# Schematic_ver01.net
KiCad netlist of a schematic drawn in Altium Designer
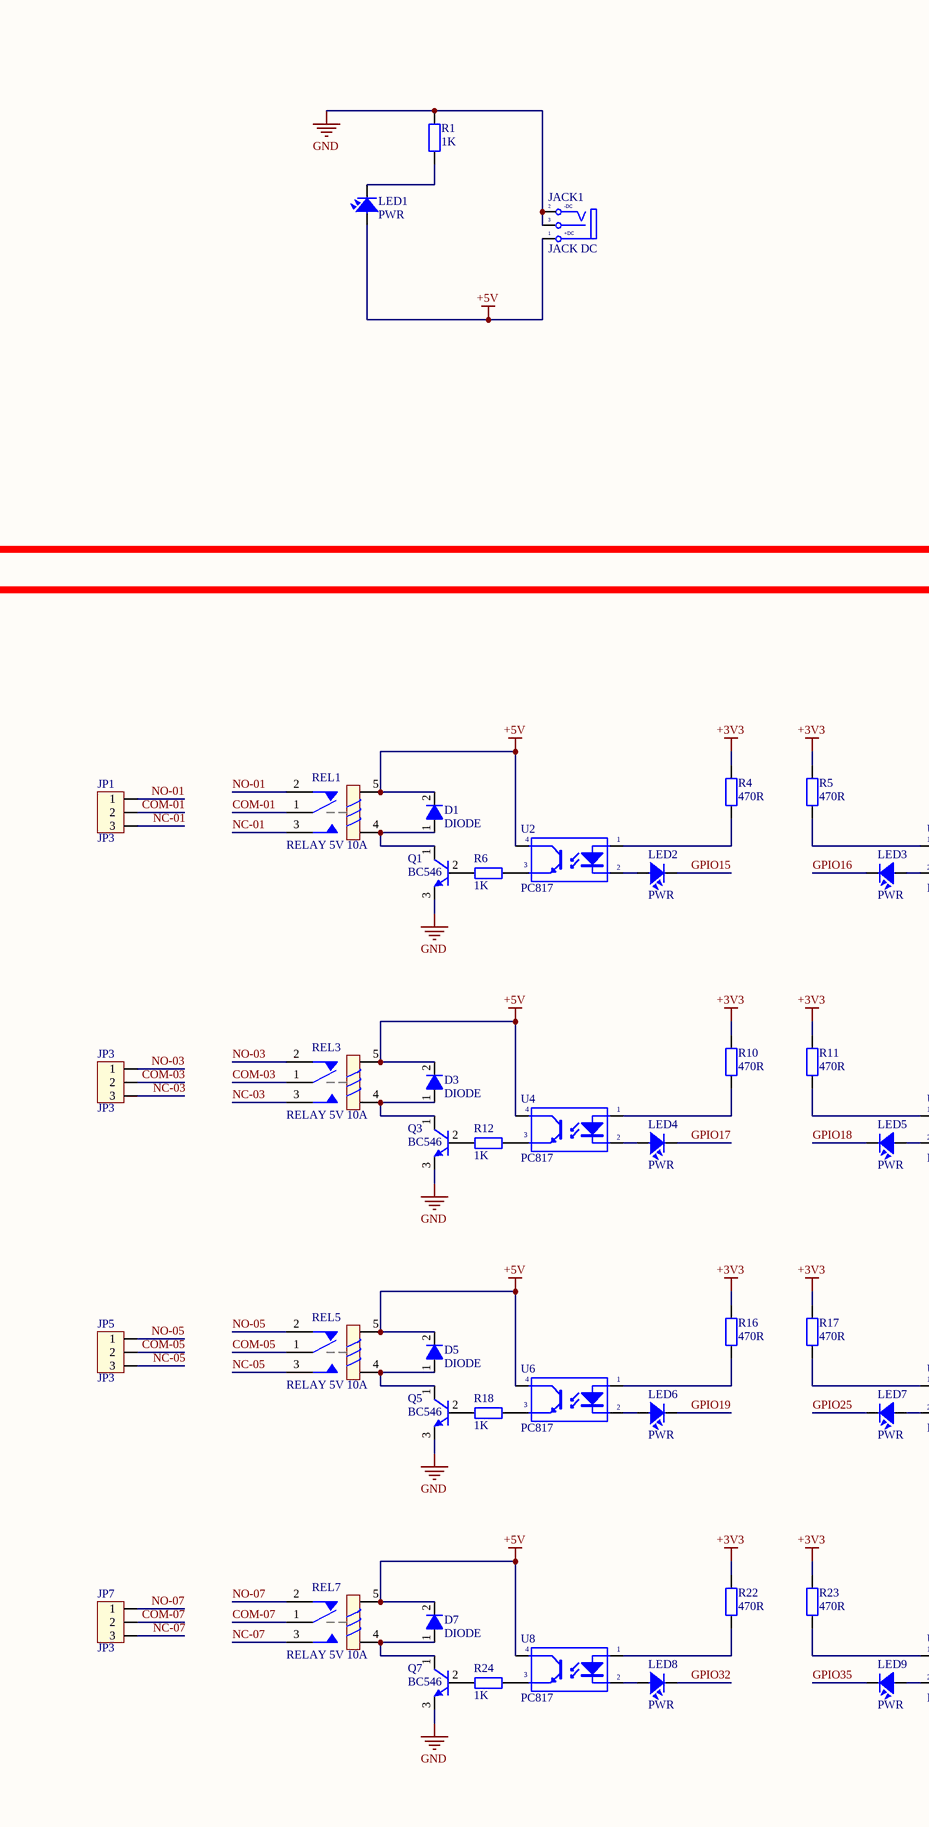
[diagram p0: Schematic_ver01.SchDoc, left]
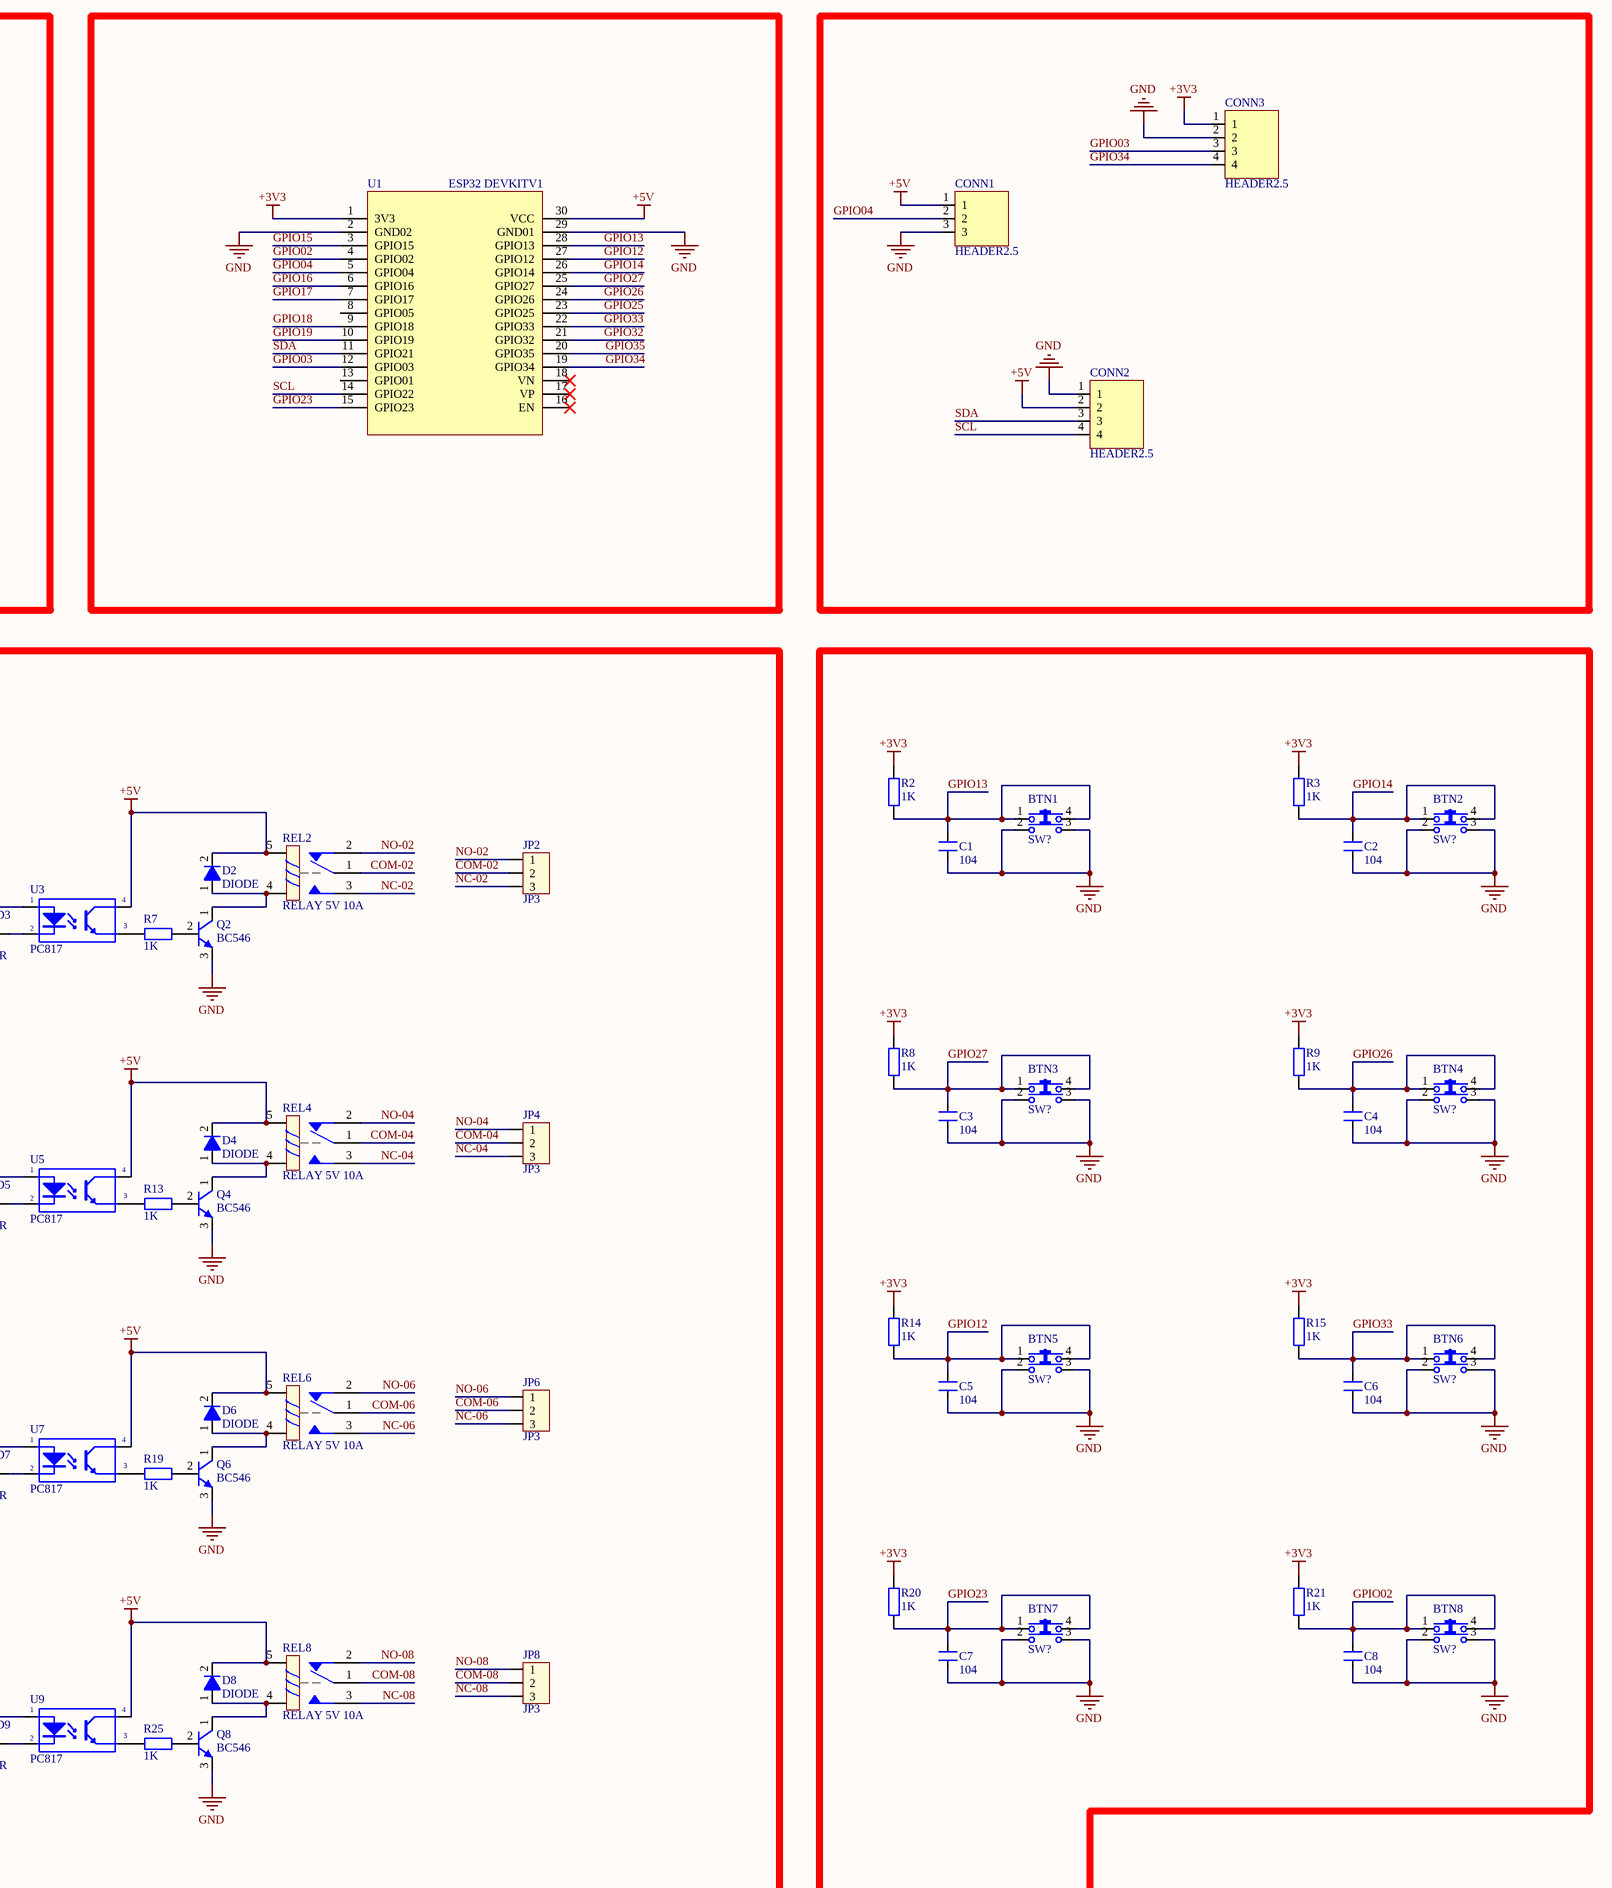
[diagram p1: Schematic_ver01.SchDoc, right]

(export (version "E")
  (design (tool "Eeschema 10.0.6"))
  (components
    (comp (ref "BTN1")
      (value "SW?")
      (footprint "SW-4P-S")
      (libsource (lib "LibSchematicAltiumKieN") (part "button-4"))
    )
    (comp (ref "BTN2")
      (value "SW?")
      (footprint "SW-4P-S")
      (libsource (lib "LibSchematicAltiumKieN") (part "button-4"))
    )
    (comp (ref "BTN3")
      (value "SW?")
      (footprint "SW-4P-S")
      (libsource (lib "LibSchematicAltiumKieN") (part "button-4"))
    )
    (comp (ref "BTN4")
      (value "SW?")
      (footprint "SW-4P-S")
      (libsource (lib "LibSchematicAltiumKieN") (part "button-4"))
    )
    (comp (ref "BTN5")
      (value "SW?")
      (footprint "SW-4P-S")
      (libsource (lib "LibSchematicAltiumKieN") (part "button-4"))
    )
    (comp (ref "BTN6")
      (value "SW?")
      (footprint "SW-4P-S")
      (libsource (lib "LibSchematicAltiumKieN") (part "button-4"))
    )
    (comp (ref "BTN7")
      (value "SW?")
      (footprint "SW-4P-S")
      (libsource (lib "LibSchematicAltiumKieN") (part "button-4"))
    )
    (comp (ref "BTN8")
      (value "SW?")
      (footprint "SW-4P-S")
      (libsource (lib "LibSchematicAltiumKieN") (part "button-4"))
    )
    (comp (ref "C1")
      (value "104")
      (footprint "0805 CAP")
      (libsource (lib "LibSchematicAltiumKieN") (part "CAP CERAMIC"))
    )
    (comp (ref "C2")
      (value "104")
      (footprint "0805 CAP")
      (libsource (lib "LibSchematicAltiumKieN") (part "CAP CERAMIC"))
    )
    (comp (ref "C3")
      (value "104")
      (footprint "0805 CAP")
      (libsource (lib "LibSchematicAltiumKieN") (part "CAP CERAMIC"))
    )
    (comp (ref "C4")
      (value "104")
      (footprint "0805 CAP")
      (libsource (lib "LibSchematicAltiumKieN") (part "CAP CERAMIC"))
    )
    (comp (ref "C5")
      (value "104")
      (footprint "0805 CAP")
      (libsource (lib "LibSchematicAltiumKieN") (part "CAP CERAMIC"))
    )
    (comp (ref "C6")
      (value "104")
      (footprint "0805 CAP")
      (libsource (lib "LibSchematicAltiumKieN") (part "CAP CERAMIC"))
    )
    (comp (ref "C7")
      (value "104")
      (footprint "0805 CAP")
      (libsource (lib "LibSchematicAltiumKieN") (part "CAP CERAMIC"))
    )
    (comp (ref "C8")
      (value "104")
      (footprint "0805 CAP")
      (libsource (lib "LibSchematicAltiumKieN") (part "CAP CERAMIC"))
    )
    (comp (ref "CONN1")
      (value "HEADER2.5")
      (footprint "CONN3")
      (description "CONN HEADER VERT 3POS 2.5MM")
      (libsource (lib "LibSchematicAltiumKieN") (part "B3B-XH-A"))
    )
    (comp (ref "CONN2")
      (value "HEADER2.5")
      (footprint "CONN4")
      (description "CONN HEADER VERT 4POS 2.5MM")
      (libsource (lib "LibSchematicAltiumKieN") (part "B4B-XH-A"))
    )
    (comp (ref "CONN3")
      (value "HEADER2.5")
      (footprint "CONN4")
      (description "CONN HEADER VERT 4POS 2.5MM")
      (libsource (lib "LibSchematicAltiumKieN") (part "B4B-XH-A"))
    )
    (comp (ref "D1")
      (value "DIODE")
      (footprint "SOD-123")
      (libsource (lib "LibSchematicAltiumKieN") (part "DIODE"))
    )
    (comp (ref "D2")
      (value "DIODE")
      (footprint "SOD-123")
      (libsource (lib "LibSchematicAltiumKieN") (part "DIODE"))
    )
    (comp (ref "D3")
      (value "DIODE")
      (footprint "SOD-123")
      (libsource (lib "LibSchematicAltiumKieN") (part "DIODE"))
    )
    (comp (ref "D4")
      (value "DIODE")
      (footprint "SOD-123")
      (libsource (lib "LibSchematicAltiumKieN") (part "DIODE"))
    )
    (comp (ref "D5")
      (value "DIODE")
      (footprint "SOD-123")
      (libsource (lib "LibSchematicAltiumKieN") (part "DIODE"))
    )
    (comp (ref "D6")
      (value "DIODE")
      (footprint "SOD-123")
      (libsource (lib "LibSchematicAltiumKieN") (part "DIODE"))
    )
    (comp (ref "D7")
      (value "DIODE")
      (footprint "SOD-123")
      (libsource (lib "LibSchematicAltiumKieN") (part "DIODE"))
    )
    (comp (ref "D8")
      (value "DIODE")
      (footprint "SOD-123")
      (libsource (lib "LibSchematicAltiumKieN") (part "DIODE"))
    )
    (comp (ref "JACK1")
      (value "JACK DC")
      (footprint "JACK-DC")
      (libsource (lib "LibSchematicAltiumKieN") (part "JACK DC"))
    )
    (comp (ref "JP1")
      (value "JP3")
      (footprint "HED3")
      (description "Connector 3")
      (libsource (lib "") (part "CON3_1"))
    )
    (comp (ref "JP2")
      (value "JP3")
      (footprint "HED3")
      (description "Connector 3")
      (libsource (lib "LibSchematicAltiumKieN") (part "CON3"))
    )
    (comp (ref "JP3")
      (value "JP3")
      (footprint "HED3")
      (description "Connector 3")
      (libsource (lib "") (part "CON3_1"))
    )
    (comp (ref "JP4")
      (value "JP3")
      (footprint "HED3")
      (description "Connector 3")
      (libsource (lib "LibSchematicAltiumKieN") (part "CON3"))
    )
    (comp (ref "JP5")
      (value "JP3")
      (footprint "HED3")
      (description "Connector 3")
      (libsource (lib "") (part "CON3_1"))
    )
    (comp (ref "JP6")
      (value "JP3")
      (footprint "HED3")
      (description "Connector 3")
      (libsource (lib "LibSchematicAltiumKieN") (part "CON3"))
    )
    (comp (ref "JP7")
      (value "JP3")
      (footprint "HED3")
      (description "Connector 3")
      (libsource (lib "") (part "CON3_1"))
    )
    (comp (ref "JP8")
      (value "JP3")
      (footprint "HED3")
      (description "Connector 3")
      (libsource (lib "LibSchematicAltiumKieN") (part "CON3"))
    )
    (comp (ref "LED1")
      (value "PWR")
      (footprint "0805 LED")
      (description "Single color LED")
      (libsource (lib "LibSchematicAltiumKieN") (part "LED"))
    )
    (comp (ref "LED2")
      (value "PWR")
      (footprint "0805 LED")
      (description "Single color LED")
      (libsource (lib "LibSchematicAltiumKieN") (part "LED"))
    )
    (comp (ref "LED3")
      (value "PWR")
      (footprint "0805 LED")
      (description "Single color LED")
      (libsource (lib "LibSchematicAltiumKieN") (part "LED"))
    )
    (comp (ref "LED4")
      (value "PWR")
      (footprint "0805 LED")
      (description "Single color LED")
      (libsource (lib "LibSchematicAltiumKieN") (part "LED"))
    )
    (comp (ref "LED5")
      (value "PWR")
      (footprint "0805 LED")
      (description "Single color LED")
      (libsource (lib "LibSchematicAltiumKieN") (part "LED"))
    )
    (comp (ref "LED6")
      (value "PWR")
      (footprint "0805 LED")
      (description "Single color LED")
      (libsource (lib "LibSchematicAltiumKieN") (part "LED"))
    )
    (comp (ref "LED7")
      (value "PWR")
      (footprint "0805 LED")
      (description "Single color LED")
      (libsource (lib "LibSchematicAltiumKieN") (part "LED"))
    )
    (comp (ref "LED8")
      (value "PWR")
      (footprint "0805 LED")
      (description "Single color LED")
      (libsource (lib "LibSchematicAltiumKieN") (part "LED"))
    )
    (comp (ref "LED9")
      (value "PWR")
      (footprint "0805 LED")
      (description "Single color LED")
      (libsource (lib "LibSchematicAltiumKieN") (part "LED"))
    )
    (comp (ref "Q1")
      (value "BC546")
      (footprint "TO92")
      (description "TRANS NPN 45V 0.1A TO-92-3")
      (libsource (lib "LibSchematicAltiumKieN") (part "BC547"))
    )
    (comp (ref "Q2")
      (value "BC546")
      (footprint "TO92")
      (description "TRANS NPN 45V 0.1A TO-92-3")
      (libsource (lib "LibSchematicAltiumKieN") (part "BC547"))
    )
    (comp (ref "Q3")
      (value "BC546")
      (footprint "TO92")
      (description "TRANS NPN 45V 0.1A TO-92-3")
      (libsource (lib "LibSchematicAltiumKieN") (part "BC547"))
    )
    (comp (ref "Q4")
      (value "BC546")
      (footprint "TO92")
      (description "TRANS NPN 45V 0.1A TO-92-3")
      (libsource (lib "LibSchematicAltiumKieN") (part "BC547"))
    )
    (comp (ref "Q5")
      (value "BC546")
      (footprint "TO92")
      (description "TRANS NPN 45V 0.1A TO-92-3")
      (libsource (lib "LibSchematicAltiumKieN") (part "BC547"))
    )
    (comp (ref "Q6")
      (value "BC546")
      (footprint "TO92")
      (description "TRANS NPN 45V 0.1A TO-92-3")
      (libsource (lib "LibSchematicAltiumKieN") (part "BC547"))
    )
    (comp (ref "Q7")
      (value "BC546")
      (footprint "TO92")
      (description "TRANS NPN 45V 0.1A TO-92-3")
      (libsource (lib "LibSchematicAltiumKieN") (part "BC547"))
    )
    (comp (ref "Q8")
      (value "BC546")
      (footprint "TO92")
      (description "TRANS NPN 45V 0.1A TO-92-3")
      (libsource (lib "LibSchematicAltiumKieN") (part "BC547"))
    )
    (comp (ref "R1")
      (value "1K")
      (footprint "0805 RESISTOR")
      (description "Resistor")
      (libsource (lib "LibSchematicAltiumKieN") (part "RESISTOR"))
    )
    (comp (ref "R2")
      (value "1K")
      (footprint "0805 RESISTOR")
      (description "Resistor")
      (libsource (lib "LibSchematicAltiumKieN") (part "RESISTOR"))
    )
    (comp (ref "R3")
      (value "1K")
      (footprint "0805 RESISTOR")
      (description "Resistor")
      (libsource (lib "LibSchematicAltiumKieN") (part "RESISTOR"))
    )
    (comp (ref "R4")
      (value "470R")
      (footprint "0805 RESISTOR")
      (description "Resistor")
      (libsource (lib "LibSchematicAltiumKieN") (part "RESISTOR"))
    )
    (comp (ref "R5")
      (value "470R")
      (footprint "0805 RESISTOR")
      (description "Resistor")
      (libsource (lib "LibSchematicAltiumKieN") (part "RESISTOR"))
    )
    (comp (ref "R6")
      (value "1K")
      (footprint "0805 RESISTOR")
      (description "Resistor")
      (libsource (lib "LibSchematicAltiumKieN") (part "RESISTOR"))
    )
    (comp (ref "R7")
      (value "1K")
      (footprint "0805 RESISTOR")
      (description "Resistor")
      (libsource (lib "LibSchematicAltiumKieN") (part "RESISTOR"))
    )
    (comp (ref "R8")
      (value "1K")
      (footprint "0805 RESISTOR")
      (description "Resistor")
      (libsource (lib "LibSchematicAltiumKieN") (part "RESISTOR"))
    )
    (comp (ref "R9")
      (value "1K")
      (footprint "0805 RESISTOR")
      (description "Resistor")
      (libsource (lib "LibSchematicAltiumKieN") (part "RESISTOR"))
    )
    (comp (ref "R10")
      (value "470R")
      (footprint "0805 RESISTOR")
      (description "Resistor")
      (libsource (lib "LibSchematicAltiumKieN") (part "RESISTOR"))
    )
    (comp (ref "R11")
      (value "470R")
      (footprint "0805 RESISTOR")
      (description "Resistor")
      (libsource (lib "LibSchematicAltiumKieN") (part "RESISTOR"))
    )
    (comp (ref "R12")
      (value "1K")
      (footprint "0805 RESISTOR")
      (description "Resistor")
      (libsource (lib "LibSchematicAltiumKieN") (part "RESISTOR"))
    )
    (comp (ref "R13")
      (value "1K")
      (footprint "0805 RESISTOR")
      (description "Resistor")
      (libsource (lib "LibSchematicAltiumKieN") (part "RESISTOR"))
    )
    (comp (ref "R14")
      (value "1K")
      (footprint "0805 RESISTOR")
      (description "Resistor")
      (libsource (lib "LibSchematicAltiumKieN") (part "RESISTOR"))
    )
    (comp (ref "R15")
      (value "1K")
      (footprint "0805 RESISTOR")
      (description "Resistor")
      (libsource (lib "LibSchematicAltiumKieN") (part "RESISTOR"))
    )
    (comp (ref "R16")
      (value "470R")
      (footprint "0805 RESISTOR")
      (description "Resistor")
      (libsource (lib "LibSchematicAltiumKieN") (part "RESISTOR"))
    )
    (comp (ref "R17")
      (value "470R")
      (footprint "0805 RESISTOR")
      (description "Resistor")
      (libsource (lib "LibSchematicAltiumKieN") (part "RESISTOR"))
    )
    (comp (ref "R18")
      (value "1K")
      (footprint "0805 RESISTOR")
      (description "Resistor")
      (libsource (lib "LibSchematicAltiumKieN") (part "RESISTOR"))
    )
    (comp (ref "R19")
      (value "1K")
      (footprint "0805 RESISTOR")
      (description "Resistor")
      (libsource (lib "LibSchematicAltiumKieN") (part "RESISTOR"))
    )
    (comp (ref "R20")
      (value "1K")
      (footprint "0805 RESISTOR")
      (description "Resistor")
      (libsource (lib "LibSchematicAltiumKieN") (part "RESISTOR"))
    )
    (comp (ref "R21")
      (value "1K")
      (footprint "0805 RESISTOR")
      (description "Resistor")
      (libsource (lib "LibSchematicAltiumKieN") (part "RESISTOR"))
    )
    (comp (ref "R22")
      (value "470R")
      (footprint "0805 RESISTOR")
      (description "Resistor")
      (libsource (lib "LibSchematicAltiumKieN") (part "RESISTOR"))
    )
    (comp (ref "R23")
      (value "470R")
      (footprint "0805 RESISTOR")
      (description "Resistor")
      (libsource (lib "LibSchematicAltiumKieN") (part "RESISTOR"))
    )
    (comp (ref "R24")
      (value "1K")
      (footprint "0805 RESISTOR")
      (description "Resistor")
      (libsource (lib "LibSchematicAltiumKieN") (part "RESISTOR"))
    )
    (comp (ref "R25")
      (value "1K")
      (footprint "0805 RESISTOR")
      (description "Resistor")
      (libsource (lib "LibSchematicAltiumKieN") (part "RESISTOR"))
    )
    (comp (ref "REL1")
      (value "RELAY 5V 10A")
      (footprint "RELAY 5V-10A")
      (libsource (lib "") (part "RELAY 5V 10A_1"))
    )
    (comp (ref "REL2")
      (value "RELAY 5V 10A")
      (footprint "RELAY 5V-10A")
      (libsource (lib "LibSchematicAltiumKieN") (part "RELAY 5V 10A"))
    )
    (comp (ref "REL3")
      (value "RELAY 5V 10A")
      (footprint "RELAY 5V-10A")
      (libsource (lib "") (part "RELAY 5V 10A_1"))
    )
    (comp (ref "REL4")
      (value "RELAY 5V 10A")
      (footprint "RELAY 5V-10A")
      (libsource (lib "LibSchematicAltiumKieN") (part "RELAY 5V 10A"))
    )
    (comp (ref "REL5")
      (value "RELAY 5V 10A")
      (footprint "RELAY 5V-10A")
      (libsource (lib "") (part "RELAY 5V 10A_1"))
    )
    (comp (ref "REL6")
      (value "RELAY 5V 10A")
      (footprint "RELAY 5V-10A")
      (libsource (lib "LibSchematicAltiumKieN") (part "RELAY 5V 10A"))
    )
    (comp (ref "REL7")
      (value "RELAY 5V 10A")
      (footprint "RELAY 5V-10A")
      (libsource (lib "") (part "RELAY 5V 10A_1"))
    )
    (comp (ref "REL8")
      (value "RELAY 5V 10A")
      (footprint "RELAY 5V-10A")
      (libsource (lib "LibSchematicAltiumKieN") (part "RELAY 5V 10A"))
    )
    (comp (ref "U1")
      (value "ESP32 DEVKITV1")
      (footprint "ESP32-PIN")
      (libsource (lib "LibSchematicAltiumKieN") (part "ESP32 DEVKITV1"))
    )
    (comp (ref "U2")
      (value "PC817")
      (footprint "DIP4/W0.3")
      (description "Single Opto")
      (libsource (lib "LibSchematicAltiumKieN") (part "PC817"))
    )
    (comp (ref "U3")
      (value "PC817")
      (footprint "DIP4/W0.3")
      (description "Single Opto")
      (libsource (lib "LibSchematicAltiumKieN") (part "PC817"))
    )
    (comp (ref "U4")
      (value "PC817")
      (footprint "DIP4/W0.3")
      (description "Single Opto")
      (libsource (lib "LibSchematicAltiumKieN") (part "PC817"))
    )
    (comp (ref "U5")
      (value "PC817")
      (footprint "DIP4/W0.3")
      (description "Single Opto")
      (libsource (lib "LibSchematicAltiumKieN") (part "PC817"))
    )
    (comp (ref "U6")
      (value "PC817")
      (footprint "DIP4/W0.3")
      (description "Single Opto")
      (libsource (lib "LibSchematicAltiumKieN") (part "PC817"))
    )
    (comp (ref "U7")
      (value "PC817")
      (footprint "DIP4/W0.3")
      (description "Single Opto")
      (libsource (lib "LibSchematicAltiumKieN") (part "PC817"))
    )
    (comp (ref "U8")
      (value "PC817")
      (footprint "DIP4/W0.3")
      (description "Single Opto")
      (libsource (lib "LibSchematicAltiumKieN") (part "PC817"))
    )
    (comp (ref "U9")
      (value "PC817")
      (footprint "DIP4/W0.3")
      (description "Single Opto")
      (libsource (lib "LibSchematicAltiumKieN") (part "PC817"))
    )
  )
  (nets
    (net (code "1") (name "+3V3") (class "Default")
      (node (ref "CONN3") (pin "1") (pinfunction "1_1") (pintype "passive"))
      (node (ref "R10") (pin "2") (pinfunction "2_2") (pintype "passive"))
      (node (ref "R11") (pin "2") (pinfunction "2_2") (pintype "passive"))
      (node (ref "R14") (pin "2") (pinfunction "2_2") (pintype "passive"))
      (node (ref "R15") (pin "2") (pinfunction "2_2") (pintype "passive"))
      (node (ref "R16") (pin "2") (pinfunction "2_2") (pintype "passive"))
      (node (ref "R17") (pin "2") (pinfunction "2_2") (pintype "passive"))
      (node (ref "R2") (pin "2") (pinfunction "2_2") (pintype "passive"))
      (node (ref "R20") (pin "2") (pinfunction "2_2") (pintype "passive"))
      (node (ref "R21") (pin "2") (pinfunction "2_2") (pintype "passive"))
      (node (ref "R22") (pin "2") (pinfunction "2_2") (pintype "passive"))
      (node (ref "R23") (pin "2") (pinfunction "2_2") (pintype "passive"))
      (node (ref "R3") (pin "2") (pinfunction "2_2") (pintype "passive"))
      (node (ref "R4") (pin "2") (pinfunction "2_2") (pintype "passive"))
      (node (ref "R5") (pin "2") (pinfunction "2_2") (pintype "passive"))
      (node (ref "R8") (pin "2") (pinfunction "2_2") (pintype "passive"))
      (node (ref "R9") (pin "2") (pinfunction "2_2") (pintype "passive"))
      (node (ref "U1") (pin "1") (pinfunction "3V3_1") (pintype "passive"))
    )
    (net (code "2") (name "+5V") (class "Default")
      (node (ref "CONN1") (pin "1") (pinfunction "1_1") (pintype "passive"))
      (node (ref "CONN2") (pin "2") (pinfunction "2_2") (pintype "passive"))
      (node (ref "D1") (pin "2") (pinfunction "A_2") (pintype "passive"))
      (node (ref "D2") (pin "2") (pinfunction "A_2") (pintype "passive"))
      (node (ref "D3") (pin "2") (pinfunction "A_2") (pintype "passive"))
      (node (ref "D4") (pin "2") (pinfunction "A_2") (pintype "passive"))
      (node (ref "D5") (pin "2") (pinfunction "A_2") (pintype "passive"))
      (node (ref "D6") (pin "2") (pinfunction "A_2") (pintype "passive"))
      (node (ref "D7") (pin "2") (pinfunction "A_2") (pintype "passive"))
      (node (ref "D8") (pin "2") (pinfunction "A_2") (pintype "passive"))
      (node (ref "JACK1") (pin "1") (pinfunction "T_1") (pintype "passive"))
      (node (ref "LED1") (pin "1") (pinfunction "1_1") (pintype "passive"))
      (node (ref "REL1") (pin "5") (pinfunction "5_5") (pintype "passive"))
      (node (ref "REL2") (pin "5") (pinfunction "5_5") (pintype "passive"))
      (node (ref "REL3") (pin "5") (pinfunction "5_5") (pintype "passive"))
      (node (ref "REL4") (pin "5") (pinfunction "5_5") (pintype "passive"))
      (node (ref "REL5") (pin "5") (pinfunction "5_5") (pintype "passive"))
      (node (ref "REL6") (pin "5") (pinfunction "5_5") (pintype "passive"))
      (node (ref "REL7") (pin "5") (pinfunction "5_5") (pintype "passive"))
      (node (ref "REL8") (pin "5") (pinfunction "5_5") (pintype "passive"))
      (node (ref "U1") (pin "30") (pinfunction "VCC_30") (pintype "passive"))
      (node (ref "U2") (pin "4") (pinfunction "C_4") (pintype "passive"))
      (node (ref "U3") (pin "4") (pinfunction "C_4") (pintype "passive"))
      (node (ref "U4") (pin "4") (pinfunction "C_4") (pintype "passive"))
      (node (ref "U5") (pin "4") (pinfunction "C_4") (pintype "passive"))
      (node (ref "U6") (pin "4") (pinfunction "C_4") (pintype "passive"))
      (node (ref "U7") (pin "4") (pinfunction "C_4") (pintype "passive"))
      (node (ref "U8") (pin "4") (pinfunction "C_4") (pintype "passive"))
      (node (ref "U9") (pin "4") (pinfunction "C_4") (pintype "passive"))
    )
    (net (code "3") (name "/COM-01") (class "Default")
      (node (ref "JP1") (pin "2") (pinfunction "2_2") (pintype "passive"))
      (node (ref "REL1") (pin "1") (pinfunction "1_1") (pintype "passive"))
    )
    (net (code "4") (name "/COM-02") (class "Default")
      (node (ref "JP2") (pin "2") (pinfunction "2_2") (pintype "passive"))
      (node (ref "REL2") (pin "1") (pinfunction "1_1") (pintype "passive"))
    )
    (net (code "5") (name "/COM-03") (class "Default")
      (node (ref "JP3") (pin "2") (pinfunction "2_2") (pintype "passive"))
      (node (ref "REL3") (pin "1") (pinfunction "1_1") (pintype "passive"))
    )
    (net (code "6") (name "/COM-04") (class "Default")
      (node (ref "JP4") (pin "2") (pinfunction "2_2") (pintype "passive"))
      (node (ref "REL4") (pin "1") (pinfunction "1_1") (pintype "passive"))
    )
    (net (code "7") (name "/COM-05") (class "Default")
      (node (ref "JP5") (pin "2") (pinfunction "2_2") (pintype "passive"))
      (node (ref "REL5") (pin "1") (pinfunction "1_1") (pintype "passive"))
    )
    (net (code "8") (name "/COM-06") (class "Default")
      (node (ref "JP6") (pin "2") (pinfunction "2_2") (pintype "passive"))
      (node (ref "REL6") (pin "1") (pinfunction "1_1") (pintype "passive"))
    )
    (net (code "9") (name "/COM-07") (class "Default")
      (node (ref "JP7") (pin "2") (pinfunction "2_2") (pintype "passive"))
      (node (ref "REL7") (pin "1") (pinfunction "1_1") (pintype "passive"))
    )
    (net (code "10") (name "/COM-08") (class "Default")
      (node (ref "JP8") (pin "2") (pinfunction "2_2") (pintype "passive"))
      (node (ref "REL8") (pin "1") (pinfunction "1_1") (pintype "passive"))
    )
    (net (code "11") (name "/GPIO02") (class "Default")
      (node (ref "BTN8") (pin "1") (pinfunction "1_1") (pintype "passive"))
      (node (ref "BTN8") (pin "4") (pinfunction "4_4") (pintype "passive"))
      (node (ref "C8") (pin "2") (pinfunction "2_2") (pintype "passive"))
      (node (ref "R21") (pin "1") (pinfunction "1_1") (pintype "passive"))
      (node (ref "U1") (pin "4") (pinfunction "GPIO02_4") (pintype "passive"))
    )
    (net (code "12") (name "/GPIO03") (class "Default")
      (node (ref "CONN3") (pin "3") (pinfunction "3_3") (pintype "passive"))
      (node (ref "U1") (pin "12") (pinfunction "GPIO03_12") (pintype "passive"))
    )
    (net (code "13") (name "/GPIO04") (class "Default")
      (node (ref "CONN1") (pin "2") (pinfunction "2_2") (pintype "passive"))
      (node (ref "U1") (pin "5") (pinfunction "GPIO04_5") (pintype "passive"))
    )
    (net (code "14") (name "/GPIO12") (class "Default")
      (node (ref "BTN5") (pin "1") (pinfunction "1_1") (pintype "passive"))
      (node (ref "BTN5") (pin "4") (pinfunction "4_4") (pintype "passive"))
      (node (ref "C5") (pin "2") (pinfunction "2_2") (pintype "passive"))
      (node (ref "R14") (pin "1") (pinfunction "1_1") (pintype "passive"))
      (node (ref "U1") (pin "27") (pinfunction "GPIO12_27") (pintype "passive"))
    )
    (net (code "15") (name "/GPIO13") (class "Default")
      (node (ref "BTN1") (pin "1") (pinfunction "1_1") (pintype "passive"))
      (node (ref "BTN1") (pin "4") (pinfunction "4_4") (pintype "passive"))
      (node (ref "C1") (pin "2") (pinfunction "2_2") (pintype "passive"))
      (node (ref "R2") (pin "1") (pinfunction "1_1") (pintype "passive"))
      (node (ref "U1") (pin "28") (pinfunction "GPIO13_28") (pintype "passive"))
    )
    (net (code "16") (name "/GPIO14") (class "Default")
      (node (ref "BTN2") (pin "1") (pinfunction "1_1") (pintype "passive"))
      (node (ref "BTN2") (pin "4") (pinfunction "4_4") (pintype "passive"))
      (node (ref "C2") (pin "2") (pinfunction "2_2") (pintype "passive"))
      (node (ref "R3") (pin "1") (pinfunction "1_1") (pintype "passive"))
      (node (ref "U1") (pin "26") (pinfunction "GPIO14_26") (pintype "passive"))
    )
    (net (code "17") (name "/GPIO15") (class "Default")
      (node (ref "LED2") (pin "2") (pinfunction "2_2") (pintype "passive"))
      (node (ref "U1") (pin "3") (pinfunction "GPIO15_3") (pintype "passive"))
    )
    (net (code "18") (name "/GPIO16") (class "Default")
      (node (ref "LED3") (pin "2") (pinfunction "2_2") (pintype "passive"))
      (node (ref "U1") (pin "6") (pinfunction "GPIO16_6") (pintype "passive"))
    )
    (net (code "19") (name "/GPIO17") (class "Default")
      (node (ref "LED4") (pin "2") (pinfunction "2_2") (pintype "passive"))
      (node (ref "U1") (pin "7") (pinfunction "GPIO17_7") (pintype "passive"))
    )
    (net (code "20") (name "/GPIO18") (class "Default")
      (node (ref "LED5") (pin "2") (pinfunction "2_2") (pintype "passive"))
      (node (ref "U1") (pin "9") (pinfunction "GPIO18_9") (pintype "passive"))
    )
    (net (code "21") (name "/GPIO19") (class "Default")
      (node (ref "LED6") (pin "2") (pinfunction "2_2") (pintype "passive"))
      (node (ref "U1") (pin "10") (pinfunction "GPIO19_10") (pintype "passive"))
    )
    (net (code "22") (name "/GPIO23") (class "Default")
      (node (ref "BTN7") (pin "1") (pinfunction "1_1") (pintype "passive"))
      (node (ref "BTN7") (pin "4") (pinfunction "4_4") (pintype "passive"))
      (node (ref "C7") (pin "2") (pinfunction "2_2") (pintype "passive"))
      (node (ref "R20") (pin "1") (pinfunction "1_1") (pintype "passive"))
      (node (ref "U1") (pin "15") (pinfunction "GPIO23_15") (pintype "passive"))
    )
    (net (code "23") (name "/GPIO25") (class "Default")
      (node (ref "LED7") (pin "2") (pinfunction "2_2") (pintype "passive"))
      (node (ref "U1") (pin "23") (pinfunction "GPIO25_23") (pintype "passive"))
    )
    (net (code "24") (name "/GPIO26") (class "Default")
      (node (ref "BTN4") (pin "1") (pinfunction "1_1") (pintype "passive"))
      (node (ref "BTN4") (pin "4") (pinfunction "4_4") (pintype "passive"))
      (node (ref "C4") (pin "2") (pinfunction "2_2") (pintype "passive"))
      (node (ref "R9") (pin "1") (pinfunction "1_1") (pintype "passive"))
      (node (ref "U1") (pin "24") (pinfunction "GPIO26_24") (pintype "passive"))
    )
    (net (code "25") (name "/GPIO27") (class "Default")
      (node (ref "BTN3") (pin "1") (pinfunction "1_1") (pintype "passive"))
      (node (ref "BTN3") (pin "4") (pinfunction "4_4") (pintype "passive"))
      (node (ref "C3") (pin "2") (pinfunction "2_2") (pintype "passive"))
      (node (ref "R8") (pin "1") (pinfunction "1_1") (pintype "passive"))
      (node (ref "U1") (pin "25") (pinfunction "GPIO27_25") (pintype "passive"))
    )
    (net (code "26") (name "/GPIO32") (class "Default")
      (node (ref "LED8") (pin "2") (pinfunction "2_2") (pintype "passive"))
      (node (ref "U1") (pin "21") (pinfunction "GPIO32_21") (pintype "passive"))
    )
    (net (code "27") (name "/GPIO33") (class "Default")
      (node (ref "BTN6") (pin "1") (pinfunction "1_1") (pintype "passive"))
      (node (ref "BTN6") (pin "4") (pinfunction "4_4") (pintype "passive"))
      (node (ref "C6") (pin "2") (pinfunction "2_2") (pintype "passive"))
      (node (ref "R15") (pin "1") (pinfunction "1_1") (pintype "passive"))
      (node (ref "U1") (pin "22") (pinfunction "GPIO33_22") (pintype "passive"))
    )
    (net (code "28") (name "/GPIO34") (class "Default")
      (node (ref "CONN3") (pin "4") (pinfunction "4_4") (pintype "passive"))
      (node (ref "U1") (pin "19") (pinfunction "GPIO34_19") (pintype "passive"))
    )
    (net (code "29") (name "/GPIO35") (class "Default")
      (node (ref "LED9") (pin "2") (pinfunction "2_2") (pintype "passive"))
      (node (ref "U1") (pin "20") (pinfunction "GPIO35_20") (pintype "passive"))
    )
    (net (code "30") (name "/NC-01") (class "Default")
      (node (ref "JP1") (pin "3") (pinfunction "3_3") (pintype "passive"))
      (node (ref "REL1") (pin "3") (pinfunction "3_3") (pintype "passive"))
    )
    (net (code "31") (name "/NC-02") (class "Default")
      (node (ref "JP2") (pin "3") (pinfunction "3_3") (pintype "passive"))
      (node (ref "REL2") (pin "3") (pinfunction "3_3") (pintype "passive"))
    )
    (net (code "32") (name "/NC-03") (class "Default")
      (node (ref "JP3") (pin "3") (pinfunction "3_3") (pintype "passive"))
      (node (ref "REL3") (pin "3") (pinfunction "3_3") (pintype "passive"))
    )
    (net (code "33") (name "/NC-04") (class "Default")
      (node (ref "JP4") (pin "3") (pinfunction "3_3") (pintype "passive"))
      (node (ref "REL4") (pin "3") (pinfunction "3_3") (pintype "passive"))
    )
    (net (code "34") (name "/NC-05") (class "Default")
      (node (ref "JP5") (pin "3") (pinfunction "3_3") (pintype "passive"))
      (node (ref "REL5") (pin "3") (pinfunction "3_3") (pintype "passive"))
    )
    (net (code "35") (name "/NC-06") (class "Default")
      (node (ref "JP6") (pin "3") (pinfunction "3_3") (pintype "passive"))
      (node (ref "REL6") (pin "3") (pinfunction "3_3") (pintype "passive"))
    )
    (net (code "36") (name "/NC-07") (class "Default")
      (node (ref "JP7") (pin "3") (pinfunction "3_3") (pintype "passive"))
      (node (ref "REL7") (pin "3") (pinfunction "3_3") (pintype "passive"))
    )
    (net (code "37") (name "/NC-08") (class "Default")
      (node (ref "JP8") (pin "3") (pinfunction "3_3") (pintype "passive"))
      (node (ref "REL8") (pin "3") (pinfunction "3_3") (pintype "passive"))
    )
    (net (code "38") (name "/NO-01") (class "Default")
      (node (ref "JP1") (pin "1") (pinfunction "1_1") (pintype "passive"))
      (node (ref "REL1") (pin "2") (pinfunction "2_2") (pintype "passive"))
    )
    (net (code "39") (name "/NO-02") (class "Default")
      (node (ref "JP2") (pin "1") (pinfunction "1_1") (pintype "passive"))
      (node (ref "REL2") (pin "2") (pinfunction "2_2") (pintype "passive"))
    )
    (net (code "40") (name "/NO-03") (class "Default")
      (node (ref "JP3") (pin "1") (pinfunction "1_1") (pintype "passive"))
      (node (ref "REL3") (pin "2") (pinfunction "2_2") (pintype "passive"))
    )
    (net (code "41") (name "/NO-04") (class "Default")
      (node (ref "JP4") (pin "1") (pinfunction "1_1") (pintype "passive"))
      (node (ref "REL4") (pin "2") (pinfunction "2_2") (pintype "passive"))
    )
    (net (code "42") (name "/NO-05") (class "Default")
      (node (ref "JP5") (pin "1") (pinfunction "1_1") (pintype "passive"))
      (node (ref "REL5") (pin "2") (pinfunction "2_2") (pintype "passive"))
    )
    (net (code "43") (name "/NO-06") (class "Default")
      (node (ref "JP6") (pin "1") (pinfunction "1_1") (pintype "passive"))
      (node (ref "REL6") (pin "2") (pinfunction "2_2") (pintype "passive"))
    )
    (net (code "44") (name "/NO-07") (class "Default")
      (node (ref "JP7") (pin "1") (pinfunction "1_1") (pintype "passive"))
      (node (ref "REL7") (pin "2") (pinfunction "2_2") (pintype "passive"))
    )
    (net (code "45") (name "/NO-08") (class "Default")
      (node (ref "JP8") (pin "1") (pinfunction "1_1") (pintype "passive"))
      (node (ref "REL8") (pin "2") (pinfunction "2_2") (pintype "passive"))
    )
    (net (code "46") (name "/SCL") (class "Default")
      (node (ref "CONN2") (pin "4") (pinfunction "4_4") (pintype "passive"))
      (node (ref "U1") (pin "14") (pinfunction "GPIO22_14") (pintype "passive"))
    )
    (net (code "47") (name "/SDA") (class "Default")
      (node (ref "CONN2") (pin "3") (pinfunction "3_3") (pintype "passive"))
      (node (ref "U1") (pin "11") (pinfunction "GPIO21_11") (pintype "passive"))
    )
    (net (code "48") (name "GND") (class "Default")
      (node (ref "BTN1") (pin "2") (pinfunction "2_2") (pintype "passive"))
      (node (ref "BTN1") (pin "3") (pinfunction "3_3") (pintype "passive"))
      (node (ref "BTN2") (pin "2") (pinfunction "2_2") (pintype "passive"))
      (node (ref "BTN2") (pin "3") (pinfunction "3_3") (pintype "passive"))
      (node (ref "BTN3") (pin "2") (pinfunction "2_2") (pintype "passive"))
      (node (ref "BTN3") (pin "3") (pinfunction "3_3") (pintype "passive"))
      (node (ref "BTN4") (pin "2") (pinfunction "2_2") (pintype "passive"))
      (node (ref "BTN4") (pin "3") (pinfunction "3_3") (pintype "passive"))
      (node (ref "BTN5") (pin "2") (pinfunction "2_2") (pintype "passive"))
      (node (ref "BTN5") (pin "3") (pinfunction "3_3") (pintype "passive"))
      (node (ref "BTN6") (pin "2") (pinfunction "2_2") (pintype "passive"))
      (node (ref "BTN6") (pin "3") (pinfunction "3_3") (pintype "passive"))
      (node (ref "BTN7") (pin "2") (pinfunction "2_2") (pintype "passive"))
      (node (ref "BTN7") (pin "3") (pinfunction "3_3") (pintype "passive"))
      (node (ref "BTN8") (pin "2") (pinfunction "2_2") (pintype "passive"))
      (node (ref "BTN8") (pin "3") (pinfunction "3_3") (pintype "passive"))
      (node (ref "C1") (pin "1") (pinfunction "1_1") (pintype "passive"))
      (node (ref "C2") (pin "1") (pinfunction "1_1") (pintype "passive"))
      (node (ref "C3") (pin "1") (pinfunction "1_1") (pintype "passive"))
      (node (ref "C4") (pin "1") (pinfunction "1_1") (pintype "passive"))
      (node (ref "C5") (pin "1") (pinfunction "1_1") (pintype "passive"))
      (node (ref "C6") (pin "1") (pinfunction "1_1") (pintype "passive"))
      (node (ref "C7") (pin "1") (pinfunction "1_1") (pintype "passive"))
      (node (ref "C8") (pin "1") (pinfunction "1_1") (pintype "passive"))
      (node (ref "CONN1") (pin "3") (pinfunction "3_3") (pintype "passive"))
      (node (ref "CONN2") (pin "1") (pinfunction "1_1") (pintype "passive"))
      (node (ref "CONN3") (pin "2") (pinfunction "2_2") (pintype "passive"))
      (node (ref "JACK1") (pin "2") (pinfunction "TN_2") (pintype "passive"))
      (node (ref "JACK1") (pin "3") (pinfunction "S_3") (pintype "power_in"))
      (node (ref "Q1") (pin "3") (pinfunction "E_3") (pintype "passive"))
      (node (ref "Q2") (pin "3") (pinfunction "E_3") (pintype "passive"))
      (node (ref "Q3") (pin "3") (pinfunction "E_3") (pintype "passive"))
      (node (ref "Q4") (pin "3") (pinfunction "E_3") (pintype "passive"))
      (node (ref "Q5") (pin "3") (pinfunction "E_3") (pintype "passive"))
      (node (ref "Q6") (pin "3") (pinfunction "E_3") (pintype "passive"))
      (node (ref "Q7") (pin "3") (pinfunction "E_3") (pintype "passive"))
      (node (ref "Q8") (pin "3") (pinfunction "E_3") (pintype "passive"))
      (node (ref "R1") (pin "2") (pinfunction "2_2") (pintype "passive"))
      (node (ref "U1") (pin "2") (pinfunction "GND02_2") (pintype "passive"))
      (node (ref "U1") (pin "29") (pinfunction "GND01_29") (pintype "passive"))
    )
    (net (code "49") (name "Net-(LED1-Pad2)") (class "Default")
      (node (ref "LED1") (pin "2") (pinfunction "2_2") (pintype "passive"))
      (node (ref "R1") (pin "1") (pinfunction "1_1") (pintype "passive"))
    )
    (net (code "50") (name "Net-(Q1-B)") (class "Default")
      (node (ref "Q1") (pin "2") (pinfunction "B_2") (pintype "passive"))
      (node (ref "R6") (pin "2") (pinfunction "2_2") (pintype "passive"))
    )
    (net (code "51") (name "Net-(Q1-C)") (class "Default")
      (node (ref "D1") (pin "1") (pinfunction "A_1") (pintype "passive"))
      (node (ref "Q1") (pin "1") (pinfunction "C_1") (pintype "passive"))
      (node (ref "REL1") (pin "4") (pinfunction "4_4") (pintype "passive"))
    )
    (net (code "52") (name "Net-(Q2-B)") (class "Default")
      (node (ref "Q2") (pin "2") (pinfunction "B_2") (pintype "passive"))
      (node (ref "R7") (pin "2") (pinfunction "2_2") (pintype "passive"))
    )
    (net (code "53") (name "Net-(Q2-C)") (class "Default")
      (node (ref "D2") (pin "1") (pinfunction "A_1") (pintype "passive"))
      (node (ref "Q2") (pin "1") (pinfunction "C_1") (pintype "passive"))
      (node (ref "REL2") (pin "4") (pinfunction "4_4") (pintype "passive"))
    )
    (net (code "54") (name "Net-(Q3-B)") (class "Default")
      (node (ref "Q3") (pin "2") (pinfunction "B_2") (pintype "passive"))
      (node (ref "R12") (pin "2") (pinfunction "2_2") (pintype "passive"))
    )
    (net (code "55") (name "Net-(Q3-C)") (class "Default")
      (node (ref "D3") (pin "1") (pinfunction "A_1") (pintype "passive"))
      (node (ref "Q3") (pin "1") (pinfunction "C_1") (pintype "passive"))
      (node (ref "REL3") (pin "4") (pinfunction "4_4") (pintype "passive"))
    )
    (net (code "56") (name "Net-(Q4-B)") (class "Default")
      (node (ref "Q4") (pin "2") (pinfunction "B_2") (pintype "passive"))
      (node (ref "R13") (pin "2") (pinfunction "2_2") (pintype "passive"))
    )
    (net (code "57") (name "Net-(Q4-C)") (class "Default")
      (node (ref "D4") (pin "1") (pinfunction "A_1") (pintype "passive"))
      (node (ref "Q4") (pin "1") (pinfunction "C_1") (pintype "passive"))
      (node (ref "REL4") (pin "4") (pinfunction "4_4") (pintype "passive"))
    )
    (net (code "58") (name "Net-(Q5-B)") (class "Default")
      (node (ref "Q5") (pin "2") (pinfunction "B_2") (pintype "passive"))
      (node (ref "R18") (pin "2") (pinfunction "2_2") (pintype "passive"))
    )
    (net (code "59") (name "Net-(Q5-C)") (class "Default")
      (node (ref "D5") (pin "1") (pinfunction "A_1") (pintype "passive"))
      (node (ref "Q5") (pin "1") (pinfunction "C_1") (pintype "passive"))
      (node (ref "REL5") (pin "4") (pinfunction "4_4") (pintype "passive"))
    )
    (net (code "60") (name "Net-(Q6-B)") (class "Default")
      (node (ref "Q6") (pin "2") (pinfunction "B_2") (pintype "passive"))
      (node (ref "R19") (pin "2") (pinfunction "2_2") (pintype "passive"))
    )
    (net (code "61") (name "Net-(Q6-C)") (class "Default")
      (node (ref "D6") (pin "1") (pinfunction "A_1") (pintype "passive"))
      (node (ref "Q6") (pin "1") (pinfunction "C_1") (pintype "passive"))
      (node (ref "REL6") (pin "4") (pinfunction "4_4") (pintype "passive"))
    )
    (net (code "62") (name "Net-(Q7-B)") (class "Default")
      (node (ref "Q7") (pin "2") (pinfunction "B_2") (pintype "passive"))
      (node (ref "R24") (pin "2") (pinfunction "2_2") (pintype "passive"))
    )
    (net (code "63") (name "Net-(Q7-C)") (class "Default")
      (node (ref "D7") (pin "1") (pinfunction "A_1") (pintype "passive"))
      (node (ref "Q7") (pin "1") (pinfunction "C_1") (pintype "passive"))
      (node (ref "REL7") (pin "4") (pinfunction "4_4") (pintype "passive"))
    )
    (net (code "64") (name "Net-(Q8-B)") (class "Default")
      (node (ref "Q8") (pin "2") (pinfunction "B_2") (pintype "passive"))
      (node (ref "R25") (pin "2") (pinfunction "2_2") (pintype "passive"))
    )
    (net (code "65") (name "Net-(Q8-C)") (class "Default")
      (node (ref "D8") (pin "1") (pinfunction "A_1") (pintype "passive"))
      (node (ref "Q8") (pin "1") (pinfunction "C_1") (pintype "passive"))
      (node (ref "REL8") (pin "4") (pinfunction "4_4") (pintype "passive"))
    )
    (net (code "66") (name "Net-(U2-A)") (class "Default")
      (node (ref "R4") (pin "1") (pinfunction "1_1") (pintype "passive"))
      (node (ref "U2") (pin "1") (pinfunction "A_1") (pintype "passive"))
    )
    (net (code "67") (name "Net-(U2-E)") (class "Default")
      (node (ref "R6") (pin "1") (pinfunction "1_1") (pintype "passive"))
      (node (ref "U2") (pin "3") (pinfunction "E_3") (pintype "passive"))
    )
    (net (code "68") (name "Net-(U2-K)") (class "Default")
      (node (ref "LED2") (pin "1") (pinfunction "1_1") (pintype "passive"))
      (node (ref "U2") (pin "2") (pinfunction "K_2") (pintype "passive"))
    )
    (net (code "69") (name "Net-(U3-A)") (class "Default")
      (node (ref "R5") (pin "1") (pinfunction "1_1") (pintype "passive"))
      (node (ref "U3") (pin "1") (pinfunction "A_1") (pintype "passive"))
    )
    (net (code "70") (name "Net-(U3-E)") (class "Default")
      (node (ref "R7") (pin "1") (pinfunction "1_1") (pintype "passive"))
      (node (ref "U3") (pin "3") (pinfunction "E_3") (pintype "passive"))
    )
    (net (code "71") (name "Net-(U3-K)") (class "Default")
      (node (ref "LED3") (pin "1") (pinfunction "1_1") (pintype "passive"))
      (node (ref "U3") (pin "2") (pinfunction "K_2") (pintype "passive"))
    )
    (net (code "72") (name "Net-(U4-A)") (class "Default")
      (node (ref "R10") (pin "1") (pinfunction "1_1") (pintype "passive"))
      (node (ref "U4") (pin "1") (pinfunction "A_1") (pintype "passive"))
    )
    (net (code "73") (name "Net-(U4-E)") (class "Default")
      (node (ref "R12") (pin "1") (pinfunction "1_1") (pintype "passive"))
      (node (ref "U4") (pin "3") (pinfunction "E_3") (pintype "passive"))
    )
    (net (code "74") (name "Net-(U4-K)") (class "Default")
      (node (ref "LED4") (pin "1") (pinfunction "1_1") (pintype "passive"))
      (node (ref "U4") (pin "2") (pinfunction "K_2") (pintype "passive"))
    )
    (net (code "75") (name "Net-(U5-A)") (class "Default")
      (node (ref "R11") (pin "1") (pinfunction "1_1") (pintype "passive"))
      (node (ref "U5") (pin "1") (pinfunction "A_1") (pintype "passive"))
    )
    (net (code "76") (name "Net-(U5-E)") (class "Default")
      (node (ref "R13") (pin "1") (pinfunction "1_1") (pintype "passive"))
      (node (ref "U5") (pin "3") (pinfunction "E_3") (pintype "passive"))
    )
    (net (code "77") (name "Net-(U5-K)") (class "Default")
      (node (ref "LED5") (pin "1") (pinfunction "1_1") (pintype "passive"))
      (node (ref "U5") (pin "2") (pinfunction "K_2") (pintype "passive"))
    )
    (net (code "78") (name "Net-(U6-A)") (class "Default")
      (node (ref "R16") (pin "1") (pinfunction "1_1") (pintype "passive"))
      (node (ref "U6") (pin "1") (pinfunction "A_1") (pintype "passive"))
    )
    (net (code "79") (name "Net-(U6-E)") (class "Default")
      (node (ref "R18") (pin "1") (pinfunction "1_1") (pintype "passive"))
      (node (ref "U6") (pin "3") (pinfunction "E_3") (pintype "passive"))
    )
    (net (code "80") (name "Net-(U6-K)") (class "Default")
      (node (ref "LED6") (pin "1") (pinfunction "1_1") (pintype "passive"))
      (node (ref "U6") (pin "2") (pinfunction "K_2") (pintype "passive"))
    )
    (net (code "81") (name "Net-(U7-A)") (class "Default")
      (node (ref "R17") (pin "1") (pinfunction "1_1") (pintype "passive"))
      (node (ref "U7") (pin "1") (pinfunction "A_1") (pintype "passive"))
    )
    (net (code "82") (name "Net-(U7-E)") (class "Default")
      (node (ref "R19") (pin "1") (pinfunction "1_1") (pintype "passive"))
      (node (ref "U7") (pin "3") (pinfunction "E_3") (pintype "passive"))
    )
    (net (code "83") (name "Net-(U7-K)") (class "Default")
      (node (ref "LED7") (pin "1") (pinfunction "1_1") (pintype "passive"))
      (node (ref "U7") (pin "2") (pinfunction "K_2") (pintype "passive"))
    )
    (net (code "84") (name "Net-(U8-A)") (class "Default")
      (node (ref "R22") (pin "1") (pinfunction "1_1") (pintype "passive"))
      (node (ref "U8") (pin "1") (pinfunction "A_1") (pintype "passive"))
    )
    (net (code "85") (name "Net-(U8-E)") (class "Default")
      (node (ref "R24") (pin "1") (pinfunction "1_1") (pintype "passive"))
      (node (ref "U8") (pin "3") (pinfunction "E_3") (pintype "passive"))
    )
    (net (code "86") (name "Net-(U8-K)") (class "Default")
      (node (ref "LED8") (pin "1") (pinfunction "1_1") (pintype "passive"))
      (node (ref "U8") (pin "2") (pinfunction "K_2") (pintype "passive"))
    )
    (net (code "87") (name "Net-(U9-A)") (class "Default")
      (node (ref "R23") (pin "1") (pinfunction "1_1") (pintype "passive"))
      (node (ref "U9") (pin "1") (pinfunction "A_1") (pintype "passive"))
    )
    (net (code "88") (name "Net-(U9-E)") (class "Default")
      (node (ref "R25") (pin "1") (pinfunction "1_1") (pintype "passive"))
      (node (ref "U9") (pin "3") (pinfunction "E_3") (pintype "passive"))
    )
    (net (code "89") (name "Net-(U9-K)") (class "Default")
      (node (ref "LED9") (pin "1") (pinfunction "1_1") (pintype "passive"))
      (node (ref "U9") (pin "2") (pinfunction "K_2") (pintype "passive"))
    )
    (net (code "90") (name "unconnected-(U1-EN-Pad16)") (class "Default")
      (node (ref "U1") (pin "16") (pinfunction "EN_16") (pintype "passive+no_connect"))
    )
    (net (code "91") (name "unconnected-(U1-GPIO01-Pad13)") (class "Default")
      (node (ref "U1") (pin "13") (pinfunction "GPIO01_13") (pintype "passive"))
    )
    (net (code "92") (name "unconnected-(U1-GPIO05-Pad8)") (class "Default")
      (node (ref "U1") (pin "8") (pinfunction "GPIO05_8") (pintype "passive"))
    )
    (net (code "93") (name "unconnected-(U1-VN-Pad18)") (class "Default")
      (node (ref "U1") (pin "18") (pinfunction "VN_18") (pintype "passive+no_connect"))
    )
    (net (code "94") (name "unconnected-(U1-VP-Pad17)") (class "Default")
      (node (ref "U1") (pin "17") (pinfunction "VP_17") (pintype "passive+no_connect"))
    )
  )
)
